# MM_2_0_power_sch.net
KiCad netlist of a schematic drawn in Altium Designer
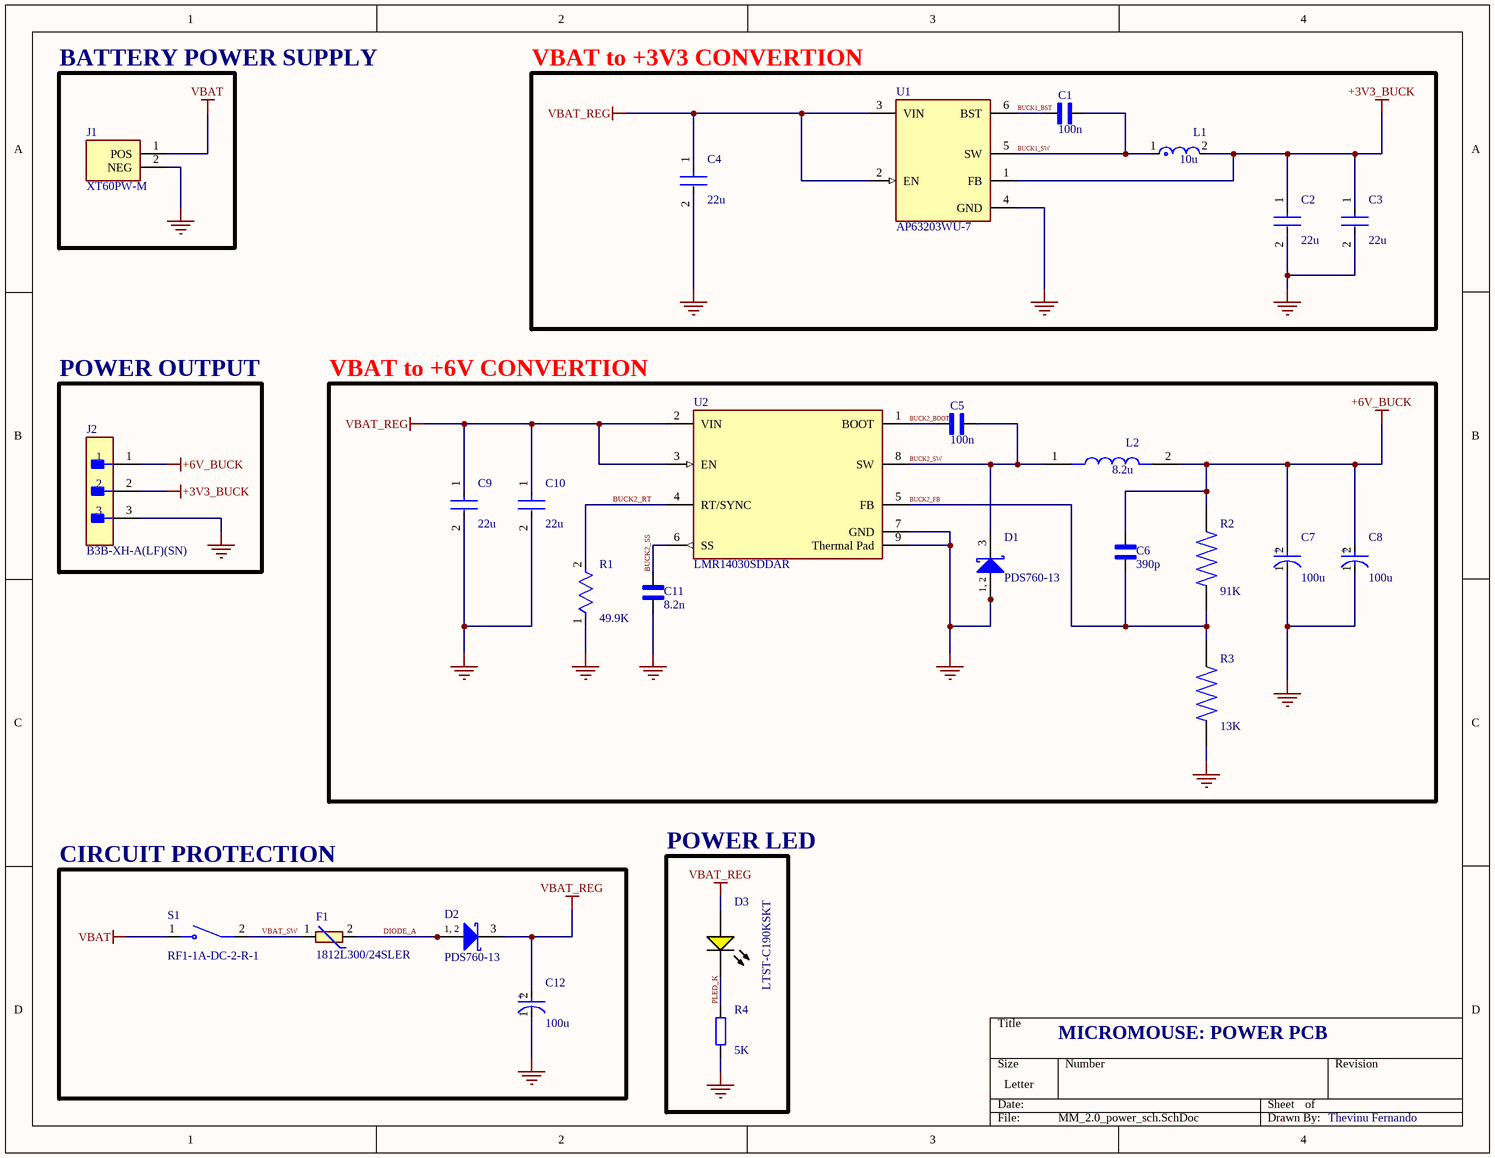
[diagram p0: MM_2.0_power_sch.SchDoc]

(export (version "E")
  (design (tool "Eeschema 10.0.6"))
  (components
    (comp (ref "C1")
      (value "100n")
      (footprint "CAP_0402")
      (description "0.1 ÂµF Â±10% 16V Ceramic Capacitor X7R 0402 (1005 Metric)")
      (fields (field (name "MF") "Samsung") (field (name "MP") "CL05B104KO5NNNC"))
      (libsource (lib "MM_2.0_schlib") (part "CL05B104KO5NNNC"))
    )
    (comp (ref "C2")
      (value "22u")
      (footprint "CAPC320160X160_CL31H-0_2_N")
      (fields
        (field (name "MOUSER PART NUMBER") "187-CL31A226KAHNNNE")
        (field (name "PART NUMBER") "CL31A226KAHNNNE")
        (field (name "DIGIKEY PART NUMBER") "1276-3047-1-ND")
      )
      (libsource (lib "MM_2.0_power_schlib") (part "CMP-13271-000012-2"))
    )
    (comp (ref "C3")
      (value "22u")
      (footprint "CAPC320160X160_CL31H-0_2_N")
      (fields
        (field (name "MOUSER PART NUMBER") "187-CL31A226KAHNNNE")
        (field (name "PART NUMBER") "CL31A226KAHNNNE")
        (field (name "DIGIKEY PART NUMBER") "1276-3047-1-ND")
      )
      (libsource (lib "MM_2.0_power_schlib") (part "CMP-13271-000012-2"))
    )
    (comp (ref "C4")
      (value "22u")
      (footprint "CAPC320160X160_CL31H-0_2_N")
      (fields
        (field (name "MOUSER PART NUMBER") "187-CL31A226KAHNNNE")
        (field (name "PART NUMBER") "CL31A226KAHNNNE")
        (field (name "DIGIKEY PART NUMBER") "1276-3047-1-ND")
      )
      (libsource (lib "MM_2.0_power_schlib") (part "CMP-13271-000012-2"))
    )
    (comp (ref "C5")
      (value "100n")
      (footprint "CAP_0402")
      (description "0.1 ÂµF Â±10% 16V Ceramic Capacitor X7R 0402 (1005 Metric)")
      (fields (field (name "MF") "Samsung") (field (name "MP") "CL05B104KO5NNNC"))
      (libsource (lib "MM_2.0_schlib") (part "CL05B104KO5NNNC"))
    )
    (comp (ref "C6")
      (value "390p")
      (footprint "CAP_0402")
      (description "0.1 ÂµF Â±10% 16V Ceramic Capacitor X7R 0402 (1005 Metric)")
      (fields (field (name "MF") "Samsung") (field (name "MP") "CL05B104KO5NNNC"))
      (libsource (lib "") (part "CL05B104KO5NNNC_1"))
    )
    (comp (ref "C7")
      (value "100u")
      (footprint "FP-OS-CON-SMT-C6-MFG")
      (description "Conductive Polymer Aluminum Solid Capacitors (OS-CON) 100uF ±20% 16V")
      (fields (field (name "VOLTAGE") "16V") (field (name "TOLERANCE") "20%"))
      (libsource (lib "MM_2.0_power_schlib") (part "CMP-05428-000037-2"))
    )
    (comp (ref "C8")
      (value "100u")
      (footprint "FP-OS-CON-SMT-C6-MFG")
      (description "Conductive Polymer Aluminum Solid Capacitors (OS-CON) 100uF ±20% 16V")
      (fields (field (name "VOLTAGE") "16V") (field (name "TOLERANCE") "20%"))
      (libsource (lib "MM_2.0_power_schlib") (part "CMP-05428-000037-2"))
    )
    (comp (ref "C9")
      (value "22u")
      (footprint "CAPC320160X160_CL31H-0_2_N")
      (fields
        (field (name "MOUSER PART NUMBER") "187-CL31A226KAHNNNE")
        (field (name "PART NUMBER") "CL31A226KAHNNNE")
        (field (name "DIGIKEY PART NUMBER") "1276-3047-1-ND")
      )
      (libsource (lib "MM_2.0_power_schlib") (part "CMP-13271-000012-2"))
    )
    (comp (ref "C10")
      (value "22u")
      (footprint "CAPC320160X160_CL31H-0_2_N")
      (fields
        (field (name "MOUSER PART NUMBER") "187-CL31A226KAHNNNE")
        (field (name "PART NUMBER") "CL31A226KAHNNNE")
        (field (name "DIGIKEY PART NUMBER") "1276-3047-1-ND")
      )
      (libsource (lib "MM_2.0_power_schlib") (part "CMP-13271-000012-2"))
    )
    (comp (ref "C11")
      (value "8.2n")
      (footprint "CAP_0402")
      (description "0.1 ÂµF Â±10% 16V Ceramic Capacitor X7R 0402 (1005 Metric)")
      (fields (field (name "MF") "Samsung") (field (name "MP") "CL05B104KO5NNNC"))
      (libsource (lib "") (part "CL05B104KO5NNNC_1"))
    )
    (comp (ref "C12")
      (value "100u")
      (footprint "FP-OS-CON-SMT-C6-MFG")
      (description "Conductive Polymer Aluminum Solid Capacitors (OS-CON) 100uF ±20% 16V")
      (fields (field (name "VOLTAGE") "16V") (field (name "TOLERANCE") "20%"))
      (libsource (lib "MM_2.0_power_schlib") (part "CMP-05428-000037-2"))
    )
    (comp (ref "D1")
      (value "PDS760-13")
      (footprint "DIOD-POWERDI5-3_V")
      (description "Schottky Barrier Rectifier, 60 V, 7 A, -65 to 150 degC, 3-Pin SMD, RoHS, Tape and Reel")
      (fields (field (name "MANUFACTURER") "Diodes Inc"))
      (libsource (lib "MM_2.0_power_schlib") (part "CMP-2000-07476-1"))
    )
    (comp (ref "D2")
      (value "PDS760-13")
      (footprint "DIOD-POWERDI5-3_V")
      (description "Schottky Barrier Rectifier, 60 V, 7 A, -65 to 150 degC, 3-Pin SMD, RoHS, Tape and Reel")
      (fields (field (name "MANUFACTURER") "Diodes Inc"))
      (libsource (lib "MM_2.0_power_schlib") (part "CMP-2000-07476-1"))
    )
    (comp (ref "D3")
      (value "LTST-C190KSKT")
      (footprint "LTST-C190KSKT_V")
      (description "LED Uni-Color Yellow, 75 mW, 30 mA, -30 to 85 degC, 2-Pin SMD, RoHS, Tape and Reel")
      (fields (field (name "TOLERANCE") "1%"))
      (libsource (lib "MM_2.0_power_schlib") (part "CMP-1674-00009-1"))
    )
    (comp (ref "F1")
      (value "1812L300/24SLER")
      (footprint "FUSSC324X455X250-2N")
      (description "Polymeric PTC Resettable Fuse 24V 3 A Ih Surface Mount 1812 (4532 Metric), Concave")
      (fields (field (name "MF") "Littelfuse Inc."))
      (libsource (lib "MM_2.0_power_schlib") (part "1812L300/24SLER"))
    )
    (comp (ref "J1")
      (value "XT60PW-M")
      (footprint "AMASS_XT60PW-M")
      (description "Socket, DC supply, male, PIN: 2")
      (fields (field (name "MF") "AMASS"))
      (libsource (lib "MM_2.0_power_schlib") (part "XT60PW-M"))
    )
    (comp (ref "J2")
      (value "B3B-XH-A(LF)(SN)")
      (footprint "FP-B3B-XH-A_LF_SN-MFG")
      (description "CONN HEADER VERT 3POS 2.5MM")
      (libsource (lib "MM_2.0_power_schlib") (part "CMP-17439-000014-3"))
    )
    (comp (ref "L1")
      (value "10u")
      (footprint "FP-VLS6045EX-100M-MFG")
      (description "FIXED IND 10UH 3.4A 61 MOHM SMD")
      (fields (field (name "TOLERANCE") "20%"))
      (libsource (lib "MM_2.0_power_schlib") (part "CMP-08253-000184-1"))
    )
    (comp (ref "L2")
      (value "8.2u")
      (footprint "IND_104CDMCCDS-8R2MC")
      (description "Inductor Power Shielded/Molded Wirewound 8.2uH 20% 100KHz Metal 8.3A 0.027Ohm DCR 4040 T/R")
      (fields (field (name "MF") "Sumida") (field (name "MP") "104CDMCCDS-8R2MC"))
      (libsource (lib "MM_2.0_power_schlib") (part "104CDMCCDS-8R2MC"))
    )
    (comp (ref "R1")
      (value "49.9K")
      (footprint "FP-ERA6A_N")
      (description "Res Thin Film 0805 49.9K Ohm 0.1% 0.125W(1/8W) +/-25ppm/ßC SMD Automotive T/R")
      (fields (field (name "TOLERANCE") "0.1%"))
      (libsource (lib "MM_2.0_power_schlib") (part "CMP-2001-00839-2"))
    )
    (comp (ref "R2")
      (value "91K")
      (footprint "RESC1608X55N")
      (description "91 kOhms Â±1% 0.1W, 1/10W Chip Resistor 0603 (1608 Metric) Moisture Resistant Thick Film")
      (fields (field (name "MF") "Yageo") (field (name "MP") "RC0603FR-0791KL"))
      (libsource (lib "MM_2.0_power_schlib") (part "RC0603FR-0791KL"))
    )
    (comp (ref "R3")
      (value "13K")
      (footprint "RESC1608X55N")
      (description "91 kOhms Â±1% 0.1W, 1/10W Chip Resistor 0603 (1608 Metric) Moisture Resistant Thick Film")
      (fields (field (name "MF") "Yageo") (field (name "MP") "RC0603FR-0791KL"))
      (libsource (lib "MM_2.0_power_schlib") (part "RC0603FR-0791KL"))
    )
    (comp (ref "R4")
      (value "5K")
      (footprint "RES_0805")
      (description "Resistor SMD 0805")
      (libsource (lib "MM_2.0_power_schlib") (part "RES_0805"))
    )
    (comp (ref "S1")
      (value "RF1-1A-DC-2-R-1")
      (footprint "SW_RF1-1A-DC-2-R-1")
      (description "Switch, Mini Rocker, 2P SPST OFF-ON, Red w/ Print, VDC ¦ Switch Components RF1-1A-DC-2-R-1")
      (fields (field (name "MF") "Switch Components"))
      (libsource (lib "MM_2.0_power_schlib") (part "RF1-1A-DC-2-R-1"))
    )
    (comp (ref "U1")
      (value "AP63203WU-7")
      (footprint "FP-TSOT26-IPC_B")
      (description "IC REG BUCK 3.3V 2A TSOT26")
      (fields
        (field (name "MANUFACTURER") "Diodes Inc.")
        (field (name "OCTOPART") "https://octopart.com/ap63203wu-7-diodes+inc.-98099550")
      )
      (libsource (lib "MM_2.0_power_schlib") (part "CMP-12757-000006-1"))
    )
    (comp (ref "U2")
      (value "LMR14030SDDAR")
      (footprint "FP-DDA0008E-MFG")
      (description "IC REG BUCK ADJ 3.5A 8SOPWR")
      (fields
        (field (name "OCTOPART") "https://octopart.com/lmr14030sddar-texas+instruments-55347267")
        (field (name "MANUFACTURER") "Texas Instruments")
      )
      (libsource (lib "MM_2.0_power_schlib") (part "CMP-04918-000074-1"))
    )
  )
  (nets
    (net (code "1") (name "+3V3_BUCK") (class "Default")
      (node (ref "C2") (pin "1") (pinfunction "1_1") (pintype "passive"))
      (node (ref "C3") (pin "1") (pinfunction "1_1") (pintype "passive"))
      (node (ref "J2") (pin "2") (pinfunction "2_2") (pintype "passive"))
      (node (ref "L1") (pin "2") (pinfunction "2_2") (pintype "passive"))
      (node (ref "U1") (pin "1") (pinfunction "FB_1") (pintype "passive"))
    )
    (net (code "2") (name "+6V_BUCK") (class "Default")
      (node (ref "C6") (pin "1") (pinfunction "1_1") (pintype "passive"))
      (node (ref "C7") (pin "2") (pinfunction "A_2") (pintype "passive"))
      (node (ref "C8") (pin "2") (pinfunction "A_2") (pintype "passive"))
      (node (ref "J2") (pin "1") (pinfunction "1_1") (pintype "passive"))
      (node (ref "L2") (pin "2") (pinfunction "2_2") (pintype "passive"))
      (node (ref "R2") (pin "2") (pinfunction "2_2") (pintype "passive"))
    )
    (net (code "3") (name "/BUCK1_BST") (class "Default")
      (node (ref "C1") (pin "2") (pinfunction "2_2") (pintype "passive"))
      (node (ref "U1") (pin "6") (pinfunction "BST_6") (pintype "passive"))
    )
    (net (code "4") (name "/BUCK1_SW") (class "Default")
      (node (ref "C1") (pin "1") (pinfunction "1_1") (pintype "passive"))
      (node (ref "L1") (pin "1") (pinfunction "1_1") (pintype "passive"))
      (node (ref "U1") (pin "5") (pinfunction "SW_5") (pintype "passive"))
    )
    (net (code "5") (name "/BUCK2_BOOT") (class "Default")
      (node (ref "C5") (pin "2") (pinfunction "2_2") (pintype "passive"))
      (node (ref "U2") (pin "1") (pinfunction "BOOT_1") (pintype "passive"))
    )
    (net (code "6") (name "/BUCK2_FB") (class "Default")
      (node (ref "C6") (pin "2") (pinfunction "2_2") (pintype "passive"))
      (node (ref "R2") (pin "1") (pinfunction "1_1") (pintype "passive"))
      (node (ref "R3") (pin "2") (pinfunction "2_2") (pintype "passive"))
      (node (ref "U2") (pin "5") (pinfunction "FB_5") (pintype "passive"))
    )
    (net (code "7") (name "/BUCK2_RT") (class "Default")
      (node (ref "R1") (pin "2") (pinfunction "2_2") (pintype "passive"))
      (node (ref "U2") (pin "4") (pinfunction "RT/SYNC_4") (pintype "passive"))
    )
    (net (code "8") (name "/BUCK2_SS") (class "Default")
      (node (ref "C11") (pin "1") (pinfunction "1_1") (pintype "passive"))
      (node (ref "U2") (pin "6") (pinfunction "SS_6") (pintype "output"))
    )
    (net (code "9") (name "/BUCK2_SW") (class "Default")
      (node (ref "C5") (pin "1") (pinfunction "1_1") (pintype "passive"))
      (node (ref "D1") (pin "3") (pinfunction "K_3") (pintype "passive"))
      (node (ref "L2") (pin "1") (pinfunction "1_1") (pintype "passive"))
      (node (ref "U2") (pin "8") (pinfunction "SW_8") (pintype "passive"))
    )
    (net (code "10") (name "/DIODE_A") (class "Default")
      (node (ref "D2") (pin "1") (pinfunction "A_1") (pintype "passive"))
      (node (ref "D2") (pin "2") (pinfunction "A_2") (pintype "passive"))
      (node (ref "F1") (pin "2") (pinfunction "2_2") (pintype "passive"))
    )
    (net (code "11") (name "/PLED_K") (class "Default")
      (node (ref "D3") (pin "2") (pinfunction "K_2") (pintype "passive"))
      (node (ref "R4") (pin "2") (pinfunction "2_2") (pintype "passive"))
    )
    (net (code "12") (name "/VBAT_SW") (class "Default")
      (node (ref "F1") (pin "1") (pinfunction "1_1") (pintype "passive"))
      (node (ref "S1") (pin "2") (pinfunction "2_2") (pintype "passive"))
    )
    (net (code "13") (name "GND") (class "Default")
      (node (ref "C10") (pin "2") (pinfunction "2_2") (pintype "passive"))
      (node (ref "C11") (pin "2") (pinfunction "2_2") (pintype "passive"))
      (node (ref "C12") (pin "1") (pinfunction "C_1") (pintype "passive"))
      (node (ref "C2") (pin "2") (pinfunction "2_2") (pintype "passive"))
      (node (ref "C3") (pin "2") (pinfunction "2_2") (pintype "passive"))
      (node (ref "C4") (pin "2") (pinfunction "2_2") (pintype "passive"))
      (node (ref "C7") (pin "1") (pinfunction "C_1") (pintype "passive"))
      (node (ref "C8") (pin "1") (pinfunction "C_1") (pintype "passive"))
      (node (ref "C9") (pin "2") (pinfunction "2_2") (pintype "passive"))
      (node (ref "D1") (pin "1") (pinfunction "A_1") (pintype "passive"))
      (node (ref "D1") (pin "2") (pinfunction "A_2") (pintype "passive"))
      (node (ref "J1") (pin "2") (pinfunction "NEG_2") (pintype "passive"))
      (node (ref "J2") (pin "3") (pinfunction "3_3") (pintype "passive"))
      (node (ref "R1") (pin "1") (pinfunction "1_1") (pintype "passive"))
      (node (ref "R3") (pin "1") (pinfunction "1_1") (pintype "passive"))
      (node (ref "R4") (pin "1") (pinfunction "1_1") (pintype "passive"))
      (node (ref "U1") (pin "4") (pinfunction "GND_4") (pintype "power_in"))
      (node (ref "U2") (pin "7") (pinfunction "GND_7") (pintype "power_in"))
      (node (ref "U2") (pin "9") (pinfunction "Thermal_Pad_9") (pintype "power_in"))
    )
    (net (code "14") (name "VBAT") (class "Default")
      (node (ref "J1") (pin "1") (pinfunction "POS_1") (pintype "passive"))
      (node (ref "S1") (pin "1") (pinfunction "1_1") (pintype "passive"))
    )
    (net (code "15") (name "VBAT_REG") (class "Default")
      (node (ref "C10") (pin "1") (pinfunction "1_1") (pintype "passive"))
      (node (ref "C12") (pin "2") (pinfunction "A_2") (pintype "passive"))
      (node (ref "C4") (pin "1") (pinfunction "1_1") (pintype "passive"))
      (node (ref "C9") (pin "1") (pinfunction "1_1") (pintype "passive"))
      (node (ref "D2") (pin "3") (pinfunction "K_3") (pintype "passive"))
      (node (ref "D3") (pin "1") (pinfunction "A_1") (pintype "passive"))
      (node (ref "U1") (pin "2") (pinfunction "EN_2") (pintype "input"))
      (node (ref "U1") (pin "3") (pinfunction "VIN_3") (pintype "power_in"))
      (node (ref "U2") (pin "2") (pinfunction "VIN_2") (pintype "power_in"))
      (node (ref "U2") (pin "3") (pinfunction "EN_3") (pintype "input"))
    )
  )
)
